# ShifterControl.net
KiCad netlist of a schematic drawn in EAGLE
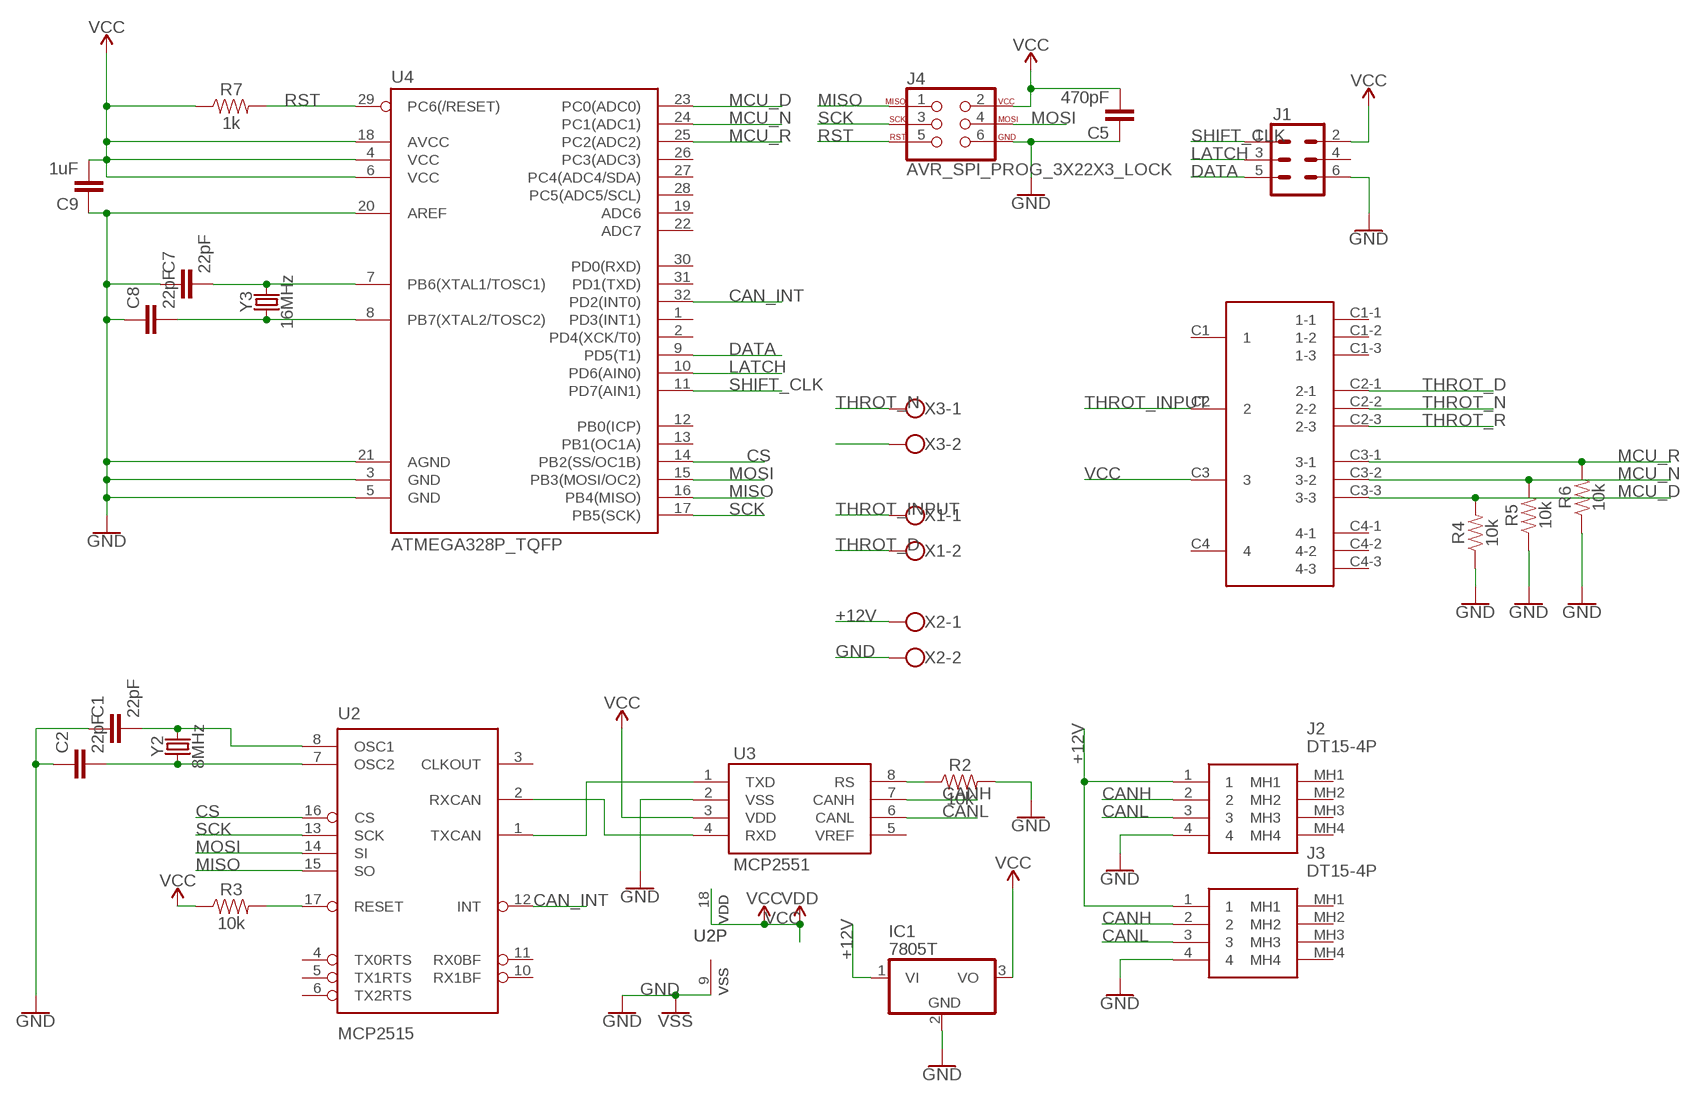
[diagram p0: schematic, sheet 1]

(export (version "E")
  (design (tool "Eeschema 10.0.6"))
  (components
    (comp (ref "C1")
      (value "22pF")
      (footprint "eagle-import:0603")
      (libsource (lib "eagle-import") (part "22PF-0603-50V-5%"))
    )
    (comp (ref "C2")
      (value "22pF")
      (footprint "eagle-import:0603")
      (libsource (lib "eagle-import") (part "22PF-0603-50V-5%"))
    )
    (comp (ref "C5")
      (value "470pF")
      (footprint "eagle-import:0603")
      (libsource (lib "eagle-import") (part "22PF-0603-50V-5%"))
    )
    (comp (ref "C7")
      (value "22pF")
      (footprint "eagle-import:0603")
      (libsource (lib "eagle-import") (part "22PF-0603-50V-5%"))
    )
    (comp (ref "C8")
      (value "22pF")
      (footprint "eagle-import:0603")
      (libsource (lib "eagle-import") (part "22PF-0603-50V-5%"))
    )
    (comp (ref "C9")
      (value "1uF")
      (footprint "eagle-import:0603")
      (libsource (lib "eagle-import") (part "22PF-0603-50V-5%"))
    )
    (comp (ref "IC1")
      (value "7805T")
      (footprint "eagle-import:TO220H")
      (libsource (lib "eagle-import") (part "78T05"))
    )
    (comp (ref "J1")
      (value "CONN_03X2SHROUD")
      (footprint "eagle-import:2X3-SHROUDED")
      (libsource (lib "eagle-import") (part "CONN_03X2SHROUD"))
    )
    (comp (ref "J2")
      (value "DT15-4P")
      (footprint "eagle-import:DT154P")
      (fields (field (name "MOUSER_PART_NUMBER") "571-DT15-4P"))
      (libsource (lib "eagle-import") (part "DT15-4P"))
    )
    (comp (ref "J3")
      (value "DT15-4P")
      (footprint "eagle-import:DT154P")
      (fields (field (name "MOUSER_PART_NUMBER") "571-DT15-4P"))
      (libsource (lib "eagle-import") (part "DT15-4P"))
    )
    (comp (ref "J4")
      (value "AVR_SPI_PROG_3X22X3_LOCK")
      (footprint "eagle-import:2X3_LOCK")
      (libsource (lib "eagle-import") (part "AVR_SPI_PROG_3X22X3_LOCK"))
    )
    (comp (ref "R2")
      (value "10k")
      (footprint "eagle-import:0603")
      (libsource (lib "eagle-import") (part "1KOHM-0603-1/10W-1%"))
    )
    (comp (ref "R3")
      (value "10k")
      (footprint "eagle-import:0603")
      (libsource (lib "eagle-import") (part "1KOHM-0603-1/10W-1%"))
    )
    (comp (ref "R4")
      (value "10k")
      (footprint "eagle-import:0603")
      (libsource (lib "eagle-import") (part "1KOHM-0603-1/10W-1%"))
    )
    (comp (ref "R5")
      (value "10k")
      (footprint "eagle-import:0603")
      (libsource (lib "eagle-import") (part "1KOHM-0603-1/10W-1%"))
    )
    (comp (ref "R6")
      (value "10k")
      (footprint "eagle-import:0603")
      (libsource (lib "eagle-import") (part "1KOHM-0603-1/10W-1%"))
    )
    (comp (ref "R7")
      (value "1k")
      (footprint "eagle-import:0603")
      (libsource (lib "eagle-import") (part "1KOHM-0603-1/10W-1%"))
    )
    (comp (ref "U$1")
      (value "SR2511F-3")
      (footprint "eagle-import:SR2511F-3")
      (libsource (lib "eagle-import") (part "SR2511F-3"))
    )
    (comp (ref "U2")
      (value "MCP2515")
      (footprint "eagle-import:SO18W")
      (libsource (lib "eagle-import") (part "MCP2515(MCP2510)SO"))
    )
    (comp (ref "U3")
      (value "MCP2551")
      (footprint "eagle-import:SO08")
      (libsource (lib "eagle-import") (part "MCP2551"))
    )
    (comp (ref "U4")
      (value "ATMEGA328P_TQFP")
      (footprint "eagle-import:TQFP32-08")
      (libsource (lib "eagle-import") (part "ATMEGA328P_TQFP"))
    )
    (comp (ref "X1")
      (value "W237-102")
      (footprint "eagle-import:W237-102")
      (fields (field (name "MPN") "237-102"))
      (libsource (lib "eagle-import") (part "W237-102"))
    )
    (comp (ref "X2")
      (value "W237-102")
      (footprint "eagle-import:W237-102")
      (fields (field (name "MPN") "237-102"))
      (libsource (lib "eagle-import") (part "W237-102"))
    )
    (comp (ref "X3")
      (value "W237-102")
      (footprint "eagle-import:W237-102")
      (fields (field (name "MPN") "237-102"))
      (libsource (lib "eagle-import") (part "W237-102"))
    )
    (comp (ref "Y2")
      (value "8MHz")
      (footprint "eagle-import:HC49UP")
      (libsource (lib "eagle-import") (part "CRYSTAL-8MHZSMD-HC49UP"))
    )
    (comp (ref "Y3")
      (value "16MHz")
      (footprint "eagle-import:HC49UP")
      (libsource (lib "eagle-import") (part "CRYSTAL-8MHZSMD-HC49UP"))
    )
  )
  (nets
    (net (code "1") (name "/+12V") (class "Default")
      (node (ref "IC1") (pin "1") (pinfunction "VI_1") (pintype "input"))
      (node (ref "J2") (pin "1") (pinfunction "1_1") (pintype "bidirectional"))
      (node (ref "J3") (pin "1") (pinfunction "1_1") (pintype "bidirectional"))
      (node (ref "X2") (pin "1") (pinfunction "KL_1") (pintype "passive"))
    )
    (net (code "2") (name "/CANH") (class "Default")
      (node (ref "J2") (pin "2") (pinfunction "2_2") (pintype "bidirectional"))
      (node (ref "J3") (pin "2") (pinfunction "2_2") (pintype "bidirectional"))
      (node (ref "U3") (pin "7") (pinfunction "CANH_7") (pintype "bidirectional"))
    )
    (net (code "3") (name "/CANL") (class "Default")
      (node (ref "J2") (pin "3") (pinfunction "3_3") (pintype "bidirectional"))
      (node (ref "J3") (pin "3") (pinfunction "3_3") (pintype "bidirectional"))
      (node (ref "U3") (pin "6") (pinfunction "CANL_6") (pintype "bidirectional"))
    )
    (net (code "4") (name "/CAN_INT") (class "Default")
      (node (ref "U2") (pin "12") (pinfunction "INT_12") (pintype "output"))
      (node (ref "U4") (pin "32") (pinfunction "PD2(INT0)_32") (pintype "bidirectional"))
    )
    (net (code "5") (name "/CS") (class "Default")
      (node (ref "U2") (pin "16") (pinfunction "CS_16") (pintype "input"))
      (node (ref "U4") (pin "14") (pinfunction "PB2(SS/OC1B)_14") (pintype "bidirectional"))
    )
    (net (code "6") (name "/DATA") (class "Default")
      (node (ref "J1") (pin "5") (pinfunction "5_5") (pintype "bidirectional"))
      (node (ref "U4") (pin "9") (pinfunction "PD5(T1)_9") (pintype "bidirectional"))
    )
    (net (code "7") (name "/LATCH") (class "Default")
      (node (ref "J1") (pin "3") (pinfunction "3_3") (pintype "bidirectional"))
      (node (ref "U4") (pin "10") (pinfunction "PD6(AIN0)_10") (pintype "bidirectional"))
    )
    (net (code "8") (name "/MCU_D") (class "Default")
      (node (ref "R4") (pin "2") (pinfunction "2_2") (pintype "passive"))
      (node (ref "U$1") (pin "C3-3") (pinfunction "3-3_C3-3") (pintype "bidirectional"))
      (node (ref "U4") (pin "23") (pinfunction "PC0(ADC0)_23") (pintype "bidirectional"))
    )
    (net (code "9") (name "/MCU_N") (class "Default")
      (node (ref "R5") (pin "2") (pinfunction "2_2") (pintype "passive"))
      (node (ref "U$1") (pin "C3-2") (pinfunction "3-2_C3-2") (pintype "bidirectional"))
      (node (ref "U4") (pin "24") (pinfunction "PC1(ADC1)_24") (pintype "bidirectional"))
    )
    (net (code "10") (name "/MCU_R") (class "Default")
      (node (ref "R6") (pin "2") (pinfunction "2_2") (pintype "passive"))
      (node (ref "U$1") (pin "C3-1") (pinfunction "3-1_C3-1") (pintype "bidirectional"))
      (node (ref "U4") (pin "25") (pinfunction "PC2(ADC2)_25") (pintype "bidirectional"))
    )
    (net (code "11") (name "/MISO") (class "Default")
      (node (ref "J4") (pin "1") (pinfunction "1_1") (pintype "passive"))
      (node (ref "U2") (pin "15") (pinfunction "SO_15") (pintype "output"))
      (node (ref "U4") (pin "16") (pinfunction "PB4(MISO)_16") (pintype "bidirectional"))
    )
    (net (code "12") (name "/MOSI") (class "Default")
      (node (ref "J4") (pin "4") (pinfunction "4_4") (pintype "passive"))
      (node (ref "U2") (pin "14") (pinfunction "SI_14") (pintype "input"))
      (node (ref "U4") (pin "15") (pinfunction "PB3(MOSI/OC2)_15") (pintype "bidirectional"))
    )
    (net (code "13") (name "/RST") (class "Default")
      (node (ref "J4") (pin "5") (pinfunction "5_5") (pintype "passive"))
      (node (ref "R7") (pin "2") (pinfunction "2_2") (pintype "passive"))
      (node (ref "U4") (pin "29") (pinfunction "PC6(/RESET)_29") (pintype "bidirectional"))
    )
    (net (code "14") (name "/SCK") (class "Default")
      (node (ref "J4") (pin "3") (pinfunction "3_3") (pintype "passive"))
      (node (ref "U2") (pin "13") (pinfunction "SCK_13") (pintype "input"))
      (node (ref "U4") (pin "17") (pinfunction "PB5(SCK)_17") (pintype "bidirectional"))
    )
    (net (code "15") (name "/SHIFT_CLK") (class "Default")
      (node (ref "J1") (pin "1") (pinfunction "1_1") (pintype "bidirectional"))
      (node (ref "U4") (pin "11") (pinfunction "PD7(AIN1)_11") (pintype "bidirectional"))
    )
    (net (code "16") (name "/THROT_D") (class "Default")
      (node (ref "U$1") (pin "C2-1") (pinfunction "2-1_C2-1") (pintype "bidirectional"))
      (node (ref "X1") (pin "2") (pinfunction "KL_2") (pintype "passive"))
    )
    (net (code "17") (name "/THROT_INPUT") (class "Default")
      (node (ref "U$1") (pin "C2") (pinfunction "2_C2") (pintype "bidirectional"))
      (node (ref "X1") (pin "1") (pinfunction "KL_1") (pintype "passive"))
    )
    (net (code "18") (name "/THROT_N") (class "Default")
      (node (ref "U$1") (pin "C2-2") (pinfunction "2-2_C2-2") (pintype "bidirectional"))
      (node (ref "X3") (pin "1") (pinfunction "KL_1") (pintype "passive"))
    )
    (net (code "19") (name "/THROT_R") (class "Default")
      (node (ref "U$1") (pin "C2-3") (pinfunction "2-3_C2-3") (pintype "bidirectional"))
      (node (ref "X3") (pin "2") (pinfunction "KL_2") (pintype "passive"))
    )
    (net (code "20") (name "GND") (class "Default")
      (node (ref "C1") (pin "1") (pinfunction "1_1") (pintype "passive"))
      (node (ref "C2") (pin "1") (pinfunction "1_1") (pintype "passive"))
      (node (ref "C5") (pin "1") (pinfunction "1_1") (pintype "passive"))
      (node (ref "C7") (pin "1") (pinfunction "1_1") (pintype "passive"))
      (node (ref "C8") (pin "1") (pinfunction "1_1") (pintype "passive"))
      (node (ref "C9") (pin "1") (pinfunction "1_1") (pintype "passive"))
      (node (ref "IC1") (pin "2") (pinfunction "GND_2") (pintype "passive"))
      (node (ref "J1") (pin "6") (pinfunction "6_6") (pintype "bidirectional"))
      (node (ref "J2") (pin "4") (pinfunction "4_4") (pintype "bidirectional"))
      (node (ref "J3") (pin "4") (pinfunction "4_4") (pintype "bidirectional"))
      (node (ref "J4") (pin "6") (pinfunction "6_6") (pintype "passive"))
      (node (ref "R2") (pin "2") (pinfunction "2_2") (pintype "passive"))
      (node (ref "R4") (pin "1") (pinfunction "1_1") (pintype "passive"))
      (node (ref "R5") (pin "1") (pinfunction "1_1") (pintype "passive"))
      (node (ref "R6") (pin "1") (pinfunction "1_1") (pintype "passive"))
      (node (ref "U2") (pin "9") (pinfunction "VSS_9") (pintype "power_in"))
      (node (ref "U3") (pin "2") (pinfunction "VSS_2") (pintype "bidirectional"))
      (node (ref "U4") (pin "20") (pinfunction "AREF_20") (pintype "bidirectional"))
      (node (ref "U4") (pin "21") (pinfunction "AGND_21") (pintype "bidirectional"))
      (node (ref "U4") (pin "3") (pinfunction "GND_3") (pintype "bidirectional"))
      (node (ref "U4") (pin "5") (pinfunction "GND_5") (pintype "bidirectional"))
      (node (ref "X2") (pin "2") (pinfunction "KL_2") (pintype "passive"))
    )
    (net (code "21") (name "Net-(U2A-OSC1)") (class "Default")
      (node (ref "C1") (pin "2") (pinfunction "2_2") (pintype "passive"))
      (node (ref "U2") (pin "8") (pinfunction "OSC1_8") (pintype "input"))
      (node (ref "Y2") (pin "2") (pinfunction "2_2") (pintype "passive"))
    )
    (net (code "22") (name "Net-(U2A-OSC2)") (class "Default")
      (node (ref "C2") (pin "2") (pinfunction "2_2") (pintype "passive"))
      (node (ref "U2") (pin "7") (pinfunction "OSC2_7") (pintype "output"))
      (node (ref "Y2") (pin "1") (pinfunction "1_1") (pintype "passive"))
    )
    (net (code "23") (name "Net-(U2A-RESET)") (class "Default")
      (node (ref "R3") (pin "2") (pinfunction "2_2") (pintype "passive"))
      (node (ref "U2") (pin "17") (pinfunction "RESET_17") (pintype "input"))
    )
    (net (code "24") (name "Net-(U2A-RXCAN)") (class "Default")
      (node (ref "U2") (pin "2") (pinfunction "RXCAN_2") (pintype "input"))
      (node (ref "U3") (pin "4") (pinfunction "RXD_4") (pintype "bidirectional"))
    )
    (net (code "25") (name "Net-(U2A-TXCAN)") (class "Default")
      (node (ref "U2") (pin "1") (pinfunction "TXCAN_1") (pintype "output"))
      (node (ref "U3") (pin "1") (pinfunction "TXD_1") (pintype "bidirectional"))
    )
    (net (code "26") (name "Net-(U3-RS)") (class "Default")
      (node (ref "R2") (pin "1") (pinfunction "1_1") (pintype "passive"))
      (node (ref "U3") (pin "8") (pinfunction "RS_8") (pintype "bidirectional"))
    )
    (net (code "27") (name "Net-(U4-PB6(XTAL1{slash}TOSC1))") (class "Default")
      (node (ref "C7") (pin "2") (pinfunction "2_2") (pintype "passive"))
      (node (ref "U4") (pin "7") (pinfunction "PB6(XTAL1/TOSC1)_7") (pintype "bidirectional"))
      (node (ref "Y3") (pin "2") (pinfunction "2_2") (pintype "passive"))
    )
    (net (code "28") (name "Net-(U4-PB7(XTAL2{slash}TOSC2))") (class "Default")
      (node (ref "C8") (pin "2") (pinfunction "2_2") (pintype "passive"))
      (node (ref "U4") (pin "8") (pinfunction "PB7(XTAL2/TOSC2)_8") (pintype "bidirectional"))
      (node (ref "Y3") (pin "1") (pinfunction "1_1") (pintype "passive"))
    )
    (net (code "29") (name "VCC") (class "Default")
      (node (ref "C5") (pin "2") (pinfunction "2_2") (pintype "passive"))
      (node (ref "C9") (pin "2") (pinfunction "2_2") (pintype "passive"))
      (node (ref "IC1") (pin "3") (pinfunction "VO_3") (pintype "passive"))
      (node (ref "J1") (pin "2") (pinfunction "2_2") (pintype "bidirectional"))
      (node (ref "J4") (pin "2") (pinfunction "2_2") (pintype "passive"))
      (node (ref "R3") (pin "1") (pinfunction "1_1") (pintype "passive"))
      (node (ref "R7") (pin "1") (pinfunction "1_1") (pintype "passive"))
      (node (ref "U$1") (pin "C3") (pinfunction "3_C3") (pintype "bidirectional"))
      (node (ref "U2") (pin "18") (pinfunction "VDD_18") (pintype "power_in"))
      (node (ref "U3") (pin "3") (pinfunction "VDD_3") (pintype "bidirectional"))
      (node (ref "U4") (pin "18") (pinfunction "AVCC_18") (pintype "bidirectional"))
      (node (ref "U4") (pin "4") (pinfunction "VCC_4") (pintype "bidirectional"))
      (node (ref "U4") (pin "6") (pinfunction "VCC_6") (pintype "bidirectional"))
    )
    (net (code "30") (name "unconnected-(J1-Pad4)") (class "Default")
      (node (ref "J1") (pin "4") (pinfunction "4_4") (pintype "bidirectional"))
    )
    (net (code "31") (name "unconnected-(J2-PadMH1)") (class "Default")
      (node (ref "J2") (pin "MH1") (pinfunction "MH1_MH1") (pintype "bidirectional"))
    )
    (net (code "32") (name "unconnected-(J2-PadMH2)") (class "Default")
      (node (ref "J2") (pin "MH2") (pinfunction "MH2_MH2") (pintype "bidirectional"))
    )
    (net (code "33") (name "unconnected-(J2-PadMH3)") (class "Default")
      (node (ref "J2") (pin "MH3") (pinfunction "MH3_MH3") (pintype "bidirectional"))
    )
    (net (code "34") (name "unconnected-(J2-PadMH4)") (class "Default")
      (node (ref "J2") (pin "MH4") (pinfunction "MH4_MH4") (pintype "bidirectional"))
    )
    (net (code "35") (name "unconnected-(J3-PadMH1)") (class "Default")
      (node (ref "J3") (pin "MH1") (pinfunction "MH1_MH1") (pintype "bidirectional"))
    )
    (net (code "36") (name "unconnected-(J3-PadMH2)") (class "Default")
      (node (ref "J3") (pin "MH2") (pinfunction "MH2_MH2") (pintype "bidirectional"))
    )
    (net (code "37") (name "unconnected-(J3-PadMH3)") (class "Default")
      (node (ref "J3") (pin "MH3") (pinfunction "MH3_MH3") (pintype "bidirectional"))
    )
    (net (code "38") (name "unconnected-(J3-PadMH4)") (class "Default")
      (node (ref "J3") (pin "MH4") (pinfunction "MH4_MH4") (pintype "bidirectional"))
    )
    (net (code "39") (name "unconnected-(U$1-1-1-PadC1-1)") (class "Default")
      (node (ref "U$1") (pin "C1-1") (pinfunction "1-1_C1-1") (pintype "bidirectional"))
    )
    (net (code "40") (name "unconnected-(U$1-1-2-PadC1-2)") (class "Default")
      (node (ref "U$1") (pin "C1-2") (pinfunction "1-2_C1-2") (pintype "bidirectional"))
    )
    (net (code "41") (name "unconnected-(U$1-1-3-PadC1-3)") (class "Default")
      (node (ref "U$1") (pin "C1-3") (pinfunction "1-3_C1-3") (pintype "bidirectional"))
    )
    (net (code "42") (name "unconnected-(U$1-1-PadC1)") (class "Default")
      (node (ref "U$1") (pin "C1") (pinfunction "1_C1") (pintype "bidirectional"))
    )
    (net (code "43") (name "unconnected-(U$1-4-1-PadC4-1)") (class "Default")
      (node (ref "U$1") (pin "C4-1") (pinfunction "4-1_C4-1") (pintype "bidirectional"))
    )
    (net (code "44") (name "unconnected-(U$1-4-2-PadC4-2)") (class "Default")
      (node (ref "U$1") (pin "C4-2") (pinfunction "4-2_C4-2") (pintype "bidirectional"))
    )
    (net (code "45") (name "unconnected-(U$1-4-3-PadC4-3)") (class "Default")
      (node (ref "U$1") (pin "C4-3") (pinfunction "4-3_C4-3") (pintype "bidirectional"))
    )
    (net (code "46") (name "unconnected-(U$1-4-PadC4)") (class "Default")
      (node (ref "U$1") (pin "C4") (pinfunction "4_C4") (pintype "bidirectional"))
    )
    (net (code "47") (name "unconnected-(U2A-CLKOUT-Pad3)") (class "Default")
      (node (ref "U2") (pin "3") (pinfunction "CLKOUT_3") (pintype "output"))
    )
    (net (code "48") (name "unconnected-(U2A-RX0BF-Pad11)") (class "Default")
      (node (ref "U2") (pin "11") (pinfunction "RX0BF_11") (pintype "output"))
    )
    (net (code "49") (name "unconnected-(U2A-RX1BF-Pad10)") (class "Default")
      (node (ref "U2") (pin "10") (pinfunction "RX1BF_10") (pintype "output"))
    )
    (net (code "50") (name "unconnected-(U2A-TX0RTS-Pad4)") (class "Default")
      (node (ref "U2") (pin "4") (pinfunction "TX0RTS_4") (pintype "input"))
    )
    (net (code "51") (name "unconnected-(U2A-TX1RTS-Pad5)") (class "Default")
      (node (ref "U2") (pin "5") (pinfunction "TX1RTS_5") (pintype "input"))
    )
    (net (code "52") (name "unconnected-(U2A-TX2RTS-Pad6)") (class "Default")
      (node (ref "U2") (pin "6") (pinfunction "TX2RTS_6") (pintype "input"))
    )
    (net (code "53") (name "unconnected-(U3-VREF-Pad5)") (class "Default")
      (node (ref "U3") (pin "5") (pinfunction "VREF_5") (pintype "bidirectional"))
    )
    (net (code "54") (name "unconnected-(U4-ADC6-Pad19)") (class "Default")
      (node (ref "U4") (pin "19") (pinfunction "ADC6_19") (pintype "bidirectional"))
    )
    (net (code "55") (name "unconnected-(U4-ADC7-Pad22)") (class "Default")
      (node (ref "U4") (pin "22") (pinfunction "ADC7_22") (pintype "bidirectional"))
    )
    (net (code "56") (name "unconnected-(U4-PB0(ICP)-Pad12)") (class "Default")
      (node (ref "U4") (pin "12") (pinfunction "PB0(ICP)_12") (pintype "bidirectional"))
    )
    (net (code "57") (name "unconnected-(U4-PB1(OC1A)-Pad13)") (class "Default")
      (node (ref "U4") (pin "13") (pinfunction "PB1(OC1A)_13") (pintype "bidirectional"))
    )
    (net (code "58") (name "unconnected-(U4-PC3(ADC3)-Pad26)") (class "Default")
      (node (ref "U4") (pin "26") (pinfunction "PC3(ADC3)_26") (pintype "bidirectional"))
    )
    (net (code "59") (name "unconnected-(U4-PC4(ADC4{slash}SDA)-Pad27)") (class "Default")
      (node (ref "U4") (pin "27") (pinfunction "PC4(ADC4/SDA)_27") (pintype "bidirectional"))
    )
    (net (code "60") (name "unconnected-(U4-PC5(ADC5{slash}SCL)-Pad28)") (class "Default")
      (node (ref "U4") (pin "28") (pinfunction "PC5(ADC5/SCL)_28") (pintype "bidirectional"))
    )
    (net (code "61") (name "unconnected-(U4-PD0(RXD)-Pad30)") (class "Default")
      (node (ref "U4") (pin "30") (pinfunction "PD0(RXD)_30") (pintype "bidirectional"))
    )
    (net (code "62") (name "unconnected-(U4-PD1(TXD)-Pad31)") (class "Default")
      (node (ref "U4") (pin "31") (pinfunction "PD1(TXD)_31") (pintype "bidirectional"))
    )
    (net (code "63") (name "unconnected-(U4-PD3(INT1)-Pad1)") (class "Default")
      (node (ref "U4") (pin "1") (pinfunction "PD3(INT1)_1") (pintype "bidirectional"))
    )
    (net (code "64") (name "unconnected-(U4-PD4(XCK{slash}T0)-Pad2)") (class "Default")
      (node (ref "U4") (pin "2") (pinfunction "PD4(XCK/T0)_2") (pintype "bidirectional"))
    )
  )
)
